# Down_Resistors.net
KiCad netlist of a schematic drawn in EAGLE
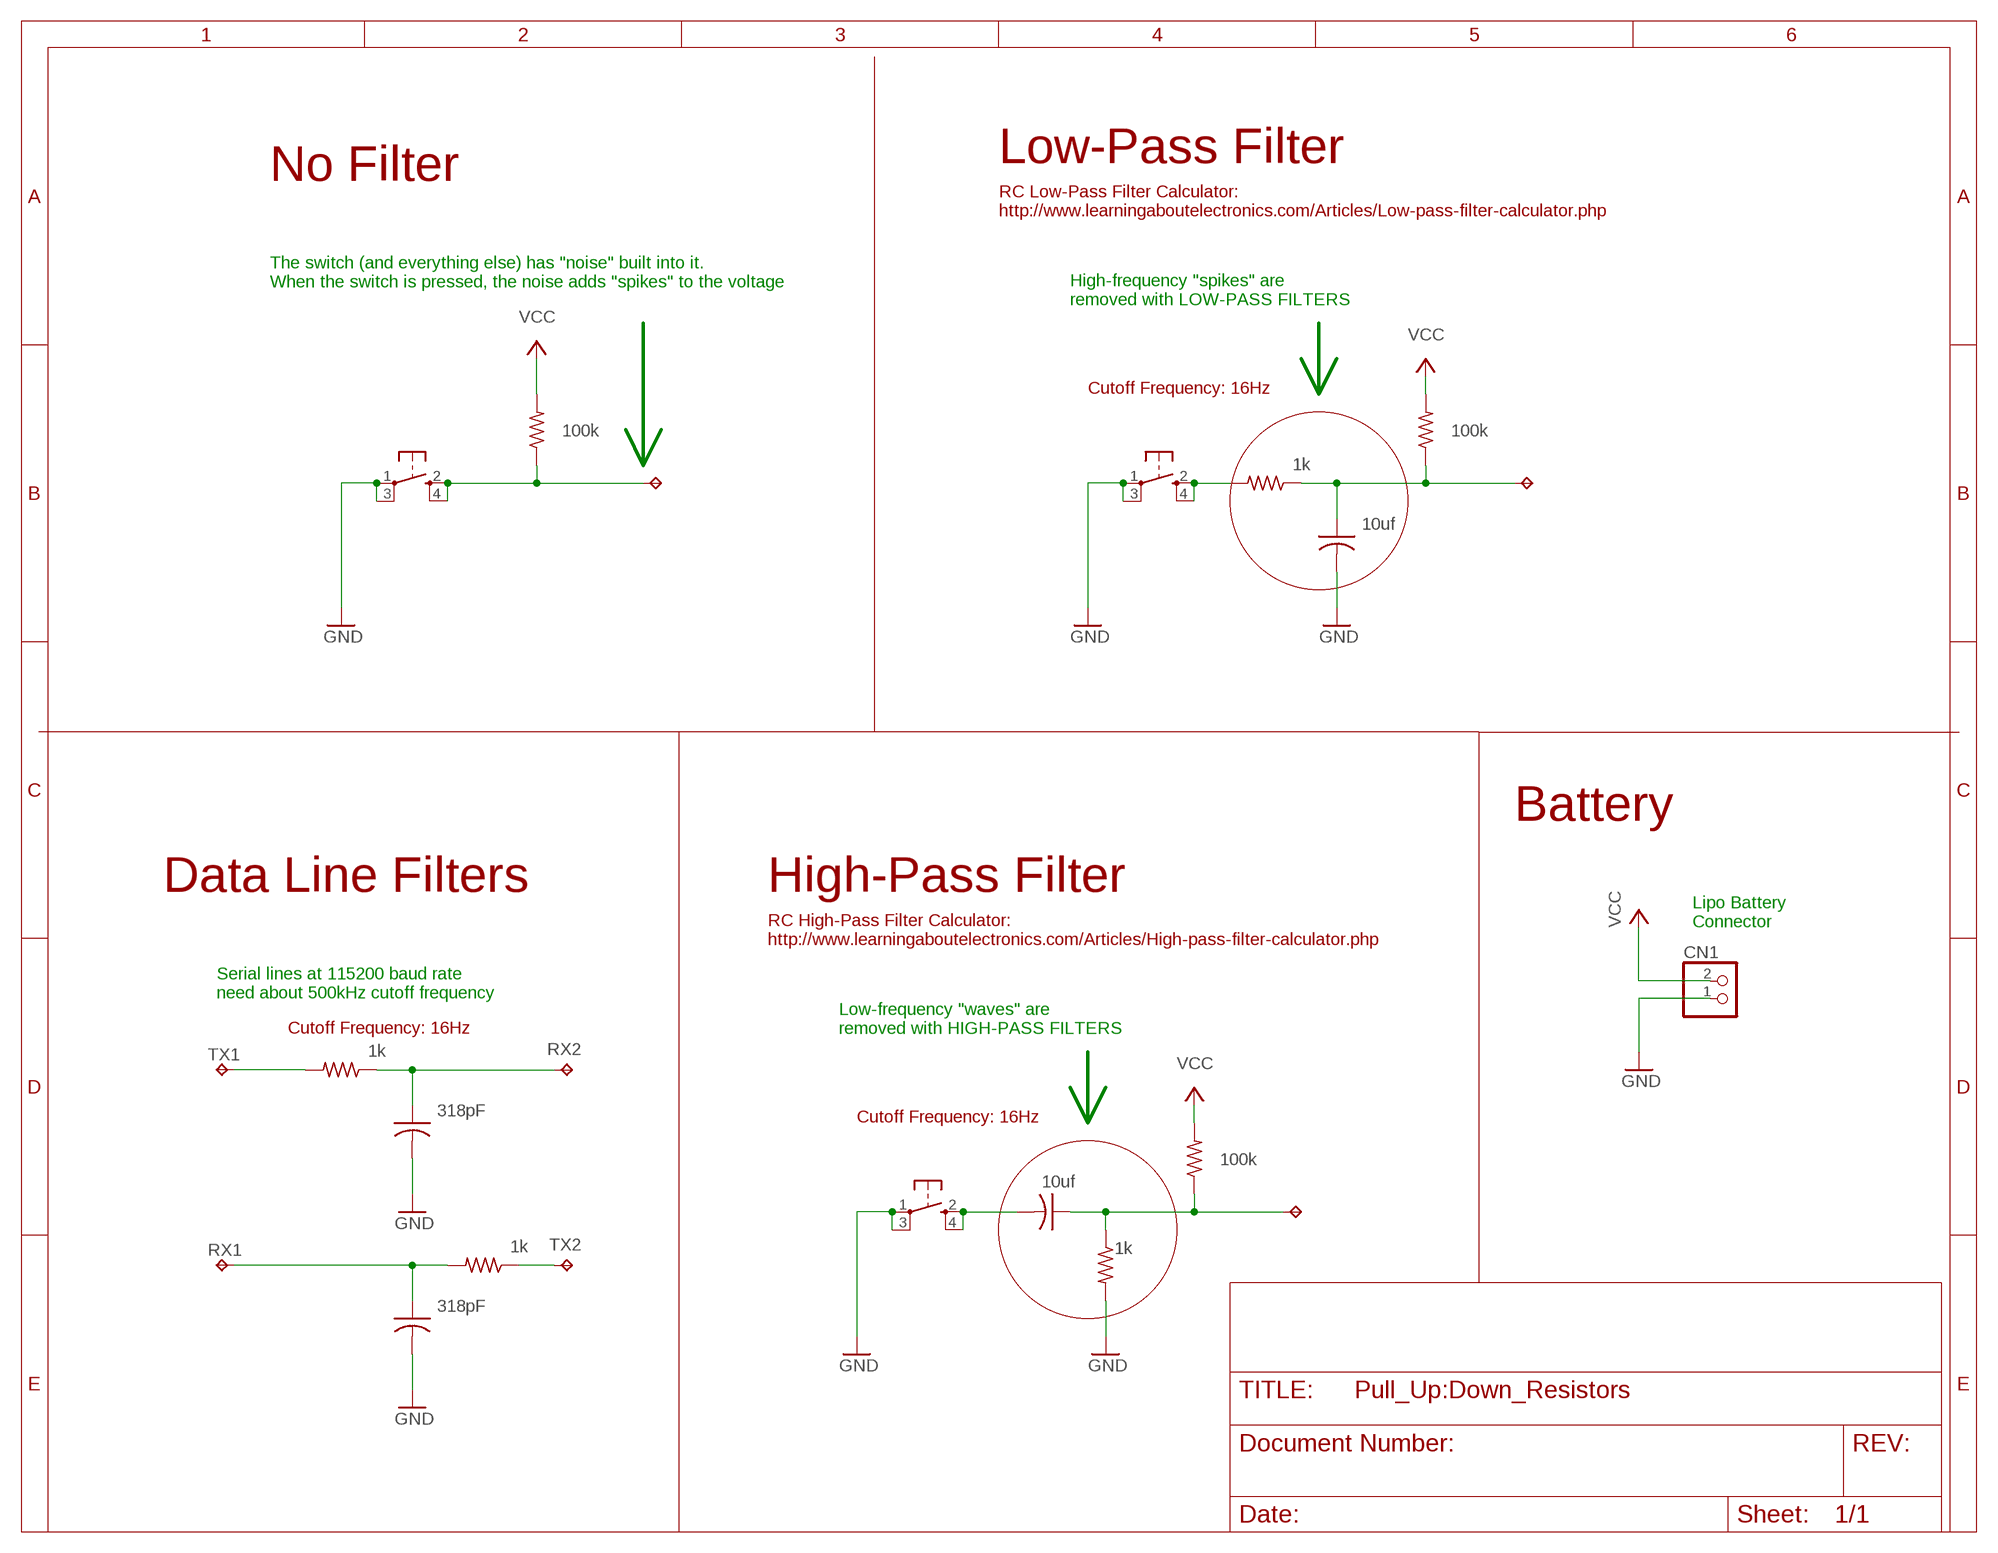
[diagram p0: schematic, sheet 1]

(export (version "E")
  (design (tool "Eeschema 10.0.6"))
  (components
    (comp (ref "C1")
      (value "10uf")
      (footprint "eagle-import:C0603")
      (libsource (lib "eagle-import") (part "C-USC0603"))
    )
    (comp (ref "C2")
      (value "318pF")
      (footprint "eagle-import:C0603")
      (libsource (lib "eagle-import") (part "C-USC0603"))
    )
    (comp (ref "C3")
      (value "318pF")
      (footprint "eagle-import:C0603")
      (libsource (lib "eagle-import") (part "C-USC0603"))
    )
    (comp (ref "C4")
      (value "10uf")
      (footprint "eagle-import:C0603")
      (libsource (lib "eagle-import") (part "C-USC0603"))
    )
    (comp (ref "CN1")
      (value "JST_2PIN-SMT-RA")
      (footprint "eagle-import:JST-PH-2-SMT-RA")
      (libsource (lib "eagle-import") (part "JST_2PIN-SMT-RA"))
    )
    (comp (ref "R1")
      (value "100k")
      (footprint "eagle-import:R0603")
      (libsource (lib "eagle-import") (part "R-US_R0603"))
    )
    (comp (ref "R2")
      (value "100k")
      (footprint "eagle-import:R0603")
      (libsource (lib "eagle-import") (part "R-US_R0603"))
    )
    (comp (ref "R3")
      (value "1k")
      (footprint "eagle-import:R0603")
      (libsource (lib "eagle-import") (part "R-US_R0603"))
    )
    (comp (ref "R4")
      (value "1k")
      (footprint "eagle-import:R0603")
      (libsource (lib "eagle-import") (part "R-US_R0603"))
    )
    (comp (ref "R5")
      (value "1k")
      (footprint "eagle-import:R0603")
      (libsource (lib "eagle-import") (part "R-US_R0603"))
    )
    (comp (ref "R6")
      (value "100k")
      (footprint "eagle-import:R0603")
      (libsource (lib "eagle-import") (part "R-US_R0603"))
    )
    (comp (ref "R7")
      (value "1k")
      (footprint "eagle-import:R0603")
      (libsource (lib "eagle-import") (part "R-US_R0603"))
    )
    (comp (ref "RX1")
      (value "TPTP20R")
      (footprint "eagle-import:TP20R")
      (libsource (lib "eagle-import") (part "TPTP20R"))
    )
    (comp (ref "RX2")
      (value "TPTP20R")
      (footprint "eagle-import:TP20R")
      (libsource (lib "eagle-import") (part "TPTP20R"))
    )
    (comp (ref "SW1")
      (value "SPST_TACT-KMR2")
      (footprint "eagle-import:KMR2")
      (libsource (lib "eagle-import") (part "SPST_TACT-KMR2"))
    )
    (comp (ref "SW2")
      (value "SPST_TACT-KMR2")
      (footprint "eagle-import:KMR2")
      (libsource (lib "eagle-import") (part "SPST_TACT-KMR2"))
    )
    (comp (ref "SW3")
      (value "SPST_TACT-KMR2")
      (footprint "eagle-import:KMR2")
      (libsource (lib "eagle-import") (part "SPST_TACT-KMR2"))
    )
    (comp (ref "TP1")
      (value "TPTP20R")
      (footprint "eagle-import:TP20R")
      (libsource (lib "eagle-import") (part "TPTP20R"))
    )
    (comp (ref "TP2")
      (value "TPTP20R")
      (footprint "eagle-import:TP20R")
      (libsource (lib "eagle-import") (part "TPTP20R"))
    )
    (comp (ref "TP3")
      (value "TPTP20R")
      (footprint "eagle-import:TP20R")
      (libsource (lib "eagle-import") (part "TPTP20R"))
    )
    (comp (ref "TX1")
      (value "TPTP20R")
      (footprint "eagle-import:TP20R")
      (libsource (lib "eagle-import") (part "TPTP20R"))
    )
    (comp (ref "TX2")
      (value "TPTP20R")
      (footprint "eagle-import:TP20R")
      (libsource (lib "eagle-import") (part "TPTP20R"))
    )
  )
  (nets
    (net (code "1") (name "GND") (class "Default")
      (node (ref "C1") (pin "2") (pinfunction "2_2") (pintype "passive"))
      (node (ref "C2") (pin "2") (pinfunction "2_2") (pintype "passive"))
      (node (ref "C3") (pin "2") (pinfunction "2_2") (pintype "passive"))
      (node (ref "CN1") (pin "1") (pinfunction "2_1") (pintype "passive"))
      (node (ref "R7") (pin "2") (pinfunction "2_2") (pintype "passive"))
      (node (ref "SW1") (pin "1") (pinfunction "P_1") (pintype "passive"))
      (node (ref "SW1") (pin "3") (pinfunction "P1_3") (pintype "passive"))
      (node (ref "SW2") (pin "1") (pinfunction "P_1") (pintype "passive"))
      (node (ref "SW2") (pin "3") (pinfunction "P1_3") (pintype "passive"))
      (node (ref "SW3") (pin "1") (pinfunction "P_1") (pintype "passive"))
      (node (ref "SW3") (pin "3") (pinfunction "P1_3") (pintype "passive"))
    )
    (net (code "2") (name "Net-(C1-Pad1)") (class "Default")
      (node (ref "C1") (pin "1") (pinfunction "1_1") (pintype "passive"))
      (node (ref "R2") (pin "1") (pinfunction "1_1") (pintype "passive"))
      (node (ref "R3") (pin "1") (pinfunction "1_1") (pintype "passive"))
      (node (ref "TP1") (pin "TP") (pinfunction "TP_TP") (pintype "input"))
    )
    (net (code "3") (name "Net-(C2-Pad1)") (class "Default")
      (node (ref "C2") (pin "1") (pinfunction "1_1") (pintype "passive"))
      (node (ref "R5") (pin "1") (pinfunction "1_1") (pintype "passive"))
      (node (ref "RX2") (pin "TP") (pinfunction "TP_TP") (pintype "input"))
    )
    (net (code "4") (name "Net-(C3-Pad1)") (class "Default")
      (node (ref "C3") (pin "1") (pinfunction "1_1") (pintype "passive"))
      (node (ref "R4") (pin "2") (pinfunction "2_2") (pintype "passive"))
      (node (ref "RX1") (pin "TP") (pinfunction "TP_TP") (pintype "input"))
    )
    (net (code "5") (name "Net-(C4-Pad1)") (class "Default")
      (node (ref "C4") (pin "1") (pinfunction "1_1") (pintype "passive"))
      (node (ref "R6") (pin "1") (pinfunction "1_1") (pintype "passive"))
      (node (ref "R7") (pin "1") (pinfunction "1_1") (pintype "passive"))
      (node (ref "TP2") (pin "TP") (pinfunction "TP_TP") (pintype "input"))
    )
    (net (code "6") (name "Net-(R4-Pad1)") (class "Default")
      (node (ref "R4") (pin "1") (pinfunction "1_1") (pintype "passive"))
      (node (ref "TX2") (pin "TP") (pinfunction "TP_TP") (pintype "input"))
    )
    (net (code "7") (name "Net-(R5-Pad2)") (class "Default")
      (node (ref "R5") (pin "2") (pinfunction "2_2") (pintype "passive"))
      (node (ref "TX1") (pin "TP") (pinfunction "TP_TP") (pintype "input"))
    )
    (net (code "8") (name "Net-(SW1-S)") (class "Default")
      (node (ref "R3") (pin "2") (pinfunction "2_2") (pintype "passive"))
      (node (ref "SW1") (pin "2") (pinfunction "S_2") (pintype "passive"))
      (node (ref "SW1") (pin "4") (pinfunction "S1_4") (pintype "passive"))
    )
    (net (code "9") (name "Net-(SW2-S)") (class "Default")
      (node (ref "C4") (pin "2") (pinfunction "2_2") (pintype "passive"))
      (node (ref "SW2") (pin "2") (pinfunction "S_2") (pintype "passive"))
      (node (ref "SW2") (pin "4") (pinfunction "S1_4") (pintype "passive"))
    )
    (net (code "10") (name "Net-(SW3-S)") (class "Default")
      (node (ref "R1") (pin "1") (pinfunction "1_1") (pintype "passive"))
      (node (ref "SW3") (pin "2") (pinfunction "S_2") (pintype "passive"))
      (node (ref "SW3") (pin "4") (pinfunction "S1_4") (pintype "passive"))
      (node (ref "TP3") (pin "TP") (pinfunction "TP_TP") (pintype "input"))
    )
    (net (code "11") (name "VCC") (class "Default")
      (node (ref "CN1") (pin "2") (pinfunction "1_2") (pintype "passive"))
      (node (ref "R1") (pin "2") (pinfunction "2_2") (pintype "passive"))
      (node (ref "R2") (pin "2") (pinfunction "2_2") (pintype "passive"))
      (node (ref "R6") (pin "2") (pinfunction "2_2") (pintype "passive"))
    )
  )
)
